# Key_Matrix.net
KiCad netlist of a schematic drawn in EAGLE
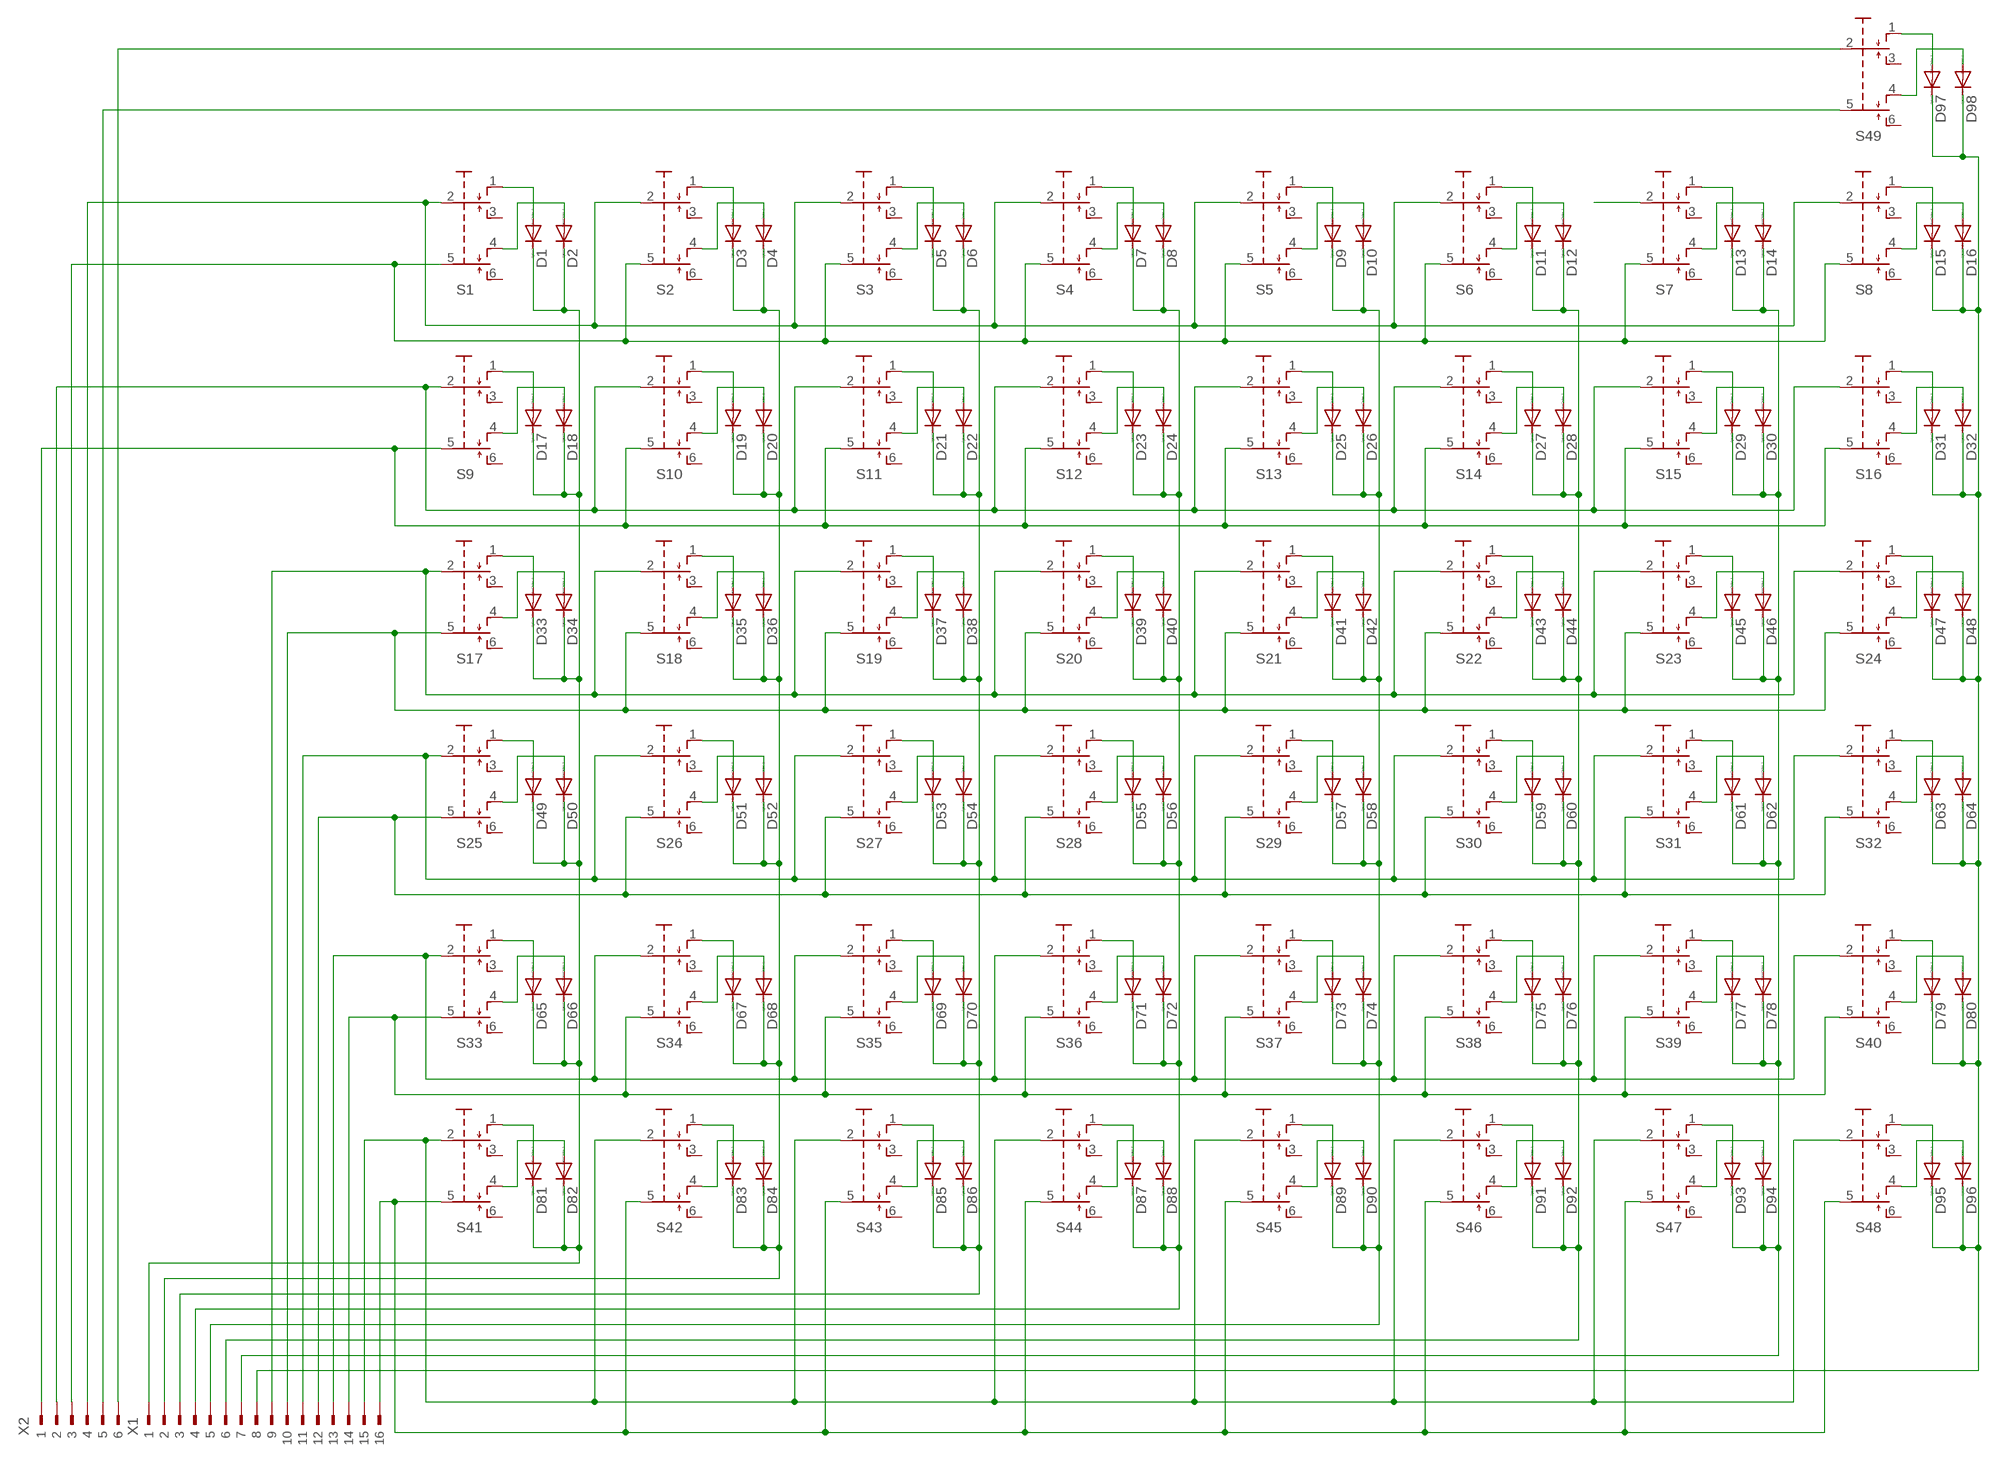
[diagram p0: schematic, sheet 1]

(export (version "E")
  (design (tool "Eeschema 10.0.6"))
  (components
    (comp (ref "D1")
      (value "1N4004")
      (footprint "eagle-import:DO41-10")
      (libsource (lib "eagle-import") (part "1N4004"))
    )
    (comp (ref "D2")
      (value "1N4004")
      (footprint "eagle-import:DO41-10")
      (libsource (lib "eagle-import") (part "1N4004"))
    )
    (comp (ref "D3")
      (value "1N4004")
      (footprint "eagle-import:DO41-10")
      (libsource (lib "eagle-import") (part "1N4004"))
    )
    (comp (ref "D4")
      (value "1N4004")
      (footprint "eagle-import:DO41-10")
      (libsource (lib "eagle-import") (part "1N4004"))
    )
    (comp (ref "D5")
      (value "1N4004")
      (footprint "eagle-import:DO41-10")
      (libsource (lib "eagle-import") (part "1N4004"))
    )
    (comp (ref "D6")
      (value "1N4004")
      (footprint "eagle-import:DO41-10")
      (libsource (lib "eagle-import") (part "1N4004"))
    )
    (comp (ref "D7")
      (value "1N4004")
      (footprint "eagle-import:DO41-10")
      (libsource (lib "eagle-import") (part "1N4004"))
    )
    (comp (ref "D8")
      (value "1N4004")
      (footprint "eagle-import:DO41-10")
      (libsource (lib "eagle-import") (part "1N4004"))
    )
    (comp (ref "D9")
      (value "1N4004")
      (footprint "eagle-import:DO41-10")
      (libsource (lib "eagle-import") (part "1N4004"))
    )
    (comp (ref "D10")
      (value "1N4004")
      (footprint "eagle-import:DO41-10")
      (libsource (lib "eagle-import") (part "1N4004"))
    )
    (comp (ref "D11")
      (value "1N4004")
      (footprint "eagle-import:DO41-10")
      (libsource (lib "eagle-import") (part "1N4004"))
    )
    (comp (ref "D12")
      (value "1N4004")
      (footprint "eagle-import:DO41-10")
      (libsource (lib "eagle-import") (part "1N4004"))
    )
    (comp (ref "D13")
      (value "1N4004")
      (footprint "eagle-import:DO41-10")
      (libsource (lib "eagle-import") (part "1N4004"))
    )
    (comp (ref "D14")
      (value "1N4004")
      (footprint "eagle-import:DO41-10")
      (libsource (lib "eagle-import") (part "1N4004"))
    )
    (comp (ref "D15")
      (value "1N4004")
      (footprint "eagle-import:DO41-10")
      (libsource (lib "eagle-import") (part "1N4004"))
    )
    (comp (ref "D16")
      (value "1N4004")
      (footprint "eagle-import:DO41-10")
      (libsource (lib "eagle-import") (part "1N4004"))
    )
    (comp (ref "D17")
      (value "1N4004")
      (footprint "eagle-import:DO41-10")
      (libsource (lib "eagle-import") (part "1N4004"))
    )
    (comp (ref "D18")
      (value "1N4004")
      (footprint "eagle-import:DO41-10")
      (libsource (lib "eagle-import") (part "1N4004"))
    )
    (comp (ref "D19")
      (value "1N4004")
      (footprint "eagle-import:DO41-10")
      (libsource (lib "eagle-import") (part "1N4004"))
    )
    (comp (ref "D20")
      (value "1N4004")
      (footprint "eagle-import:DO41-10")
      (libsource (lib "eagle-import") (part "1N4004"))
    )
    (comp (ref "D21")
      (value "1N4004")
      (footprint "eagle-import:DO41-10")
      (libsource (lib "eagle-import") (part "1N4004"))
    )
    (comp (ref "D22")
      (value "1N4004")
      (footprint "eagle-import:DO41-10")
      (libsource (lib "eagle-import") (part "1N4004"))
    )
    (comp (ref "D23")
      (value "1N4004")
      (footprint "eagle-import:DO41-10")
      (libsource (lib "eagle-import") (part "1N4004"))
    )
    (comp (ref "D24")
      (value "1N4004")
      (footprint "eagle-import:DO41-10")
      (libsource (lib "eagle-import") (part "1N4004"))
    )
    (comp (ref "D25")
      (value "1N4004")
      (footprint "eagle-import:DO41-10")
      (libsource (lib "eagle-import") (part "1N4004"))
    )
    (comp (ref "D26")
      (value "1N4004")
      (footprint "eagle-import:DO41-10")
      (libsource (lib "eagle-import") (part "1N4004"))
    )
    (comp (ref "D27")
      (value "1N4004")
      (footprint "eagle-import:DO41-10")
      (libsource (lib "eagle-import") (part "1N4004"))
    )
    (comp (ref "D28")
      (value "1N4004")
      (footprint "eagle-import:DO41-10")
      (libsource (lib "eagle-import") (part "1N4004"))
    )
    (comp (ref "D29")
      (value "1N4004")
      (footprint "eagle-import:DO41-10")
      (libsource (lib "eagle-import") (part "1N4004"))
    )
    (comp (ref "D30")
      (value "1N4004")
      (footprint "eagle-import:DO41-10")
      (libsource (lib "eagle-import") (part "1N4004"))
    )
    (comp (ref "D31")
      (value "1N4004")
      (footprint "eagle-import:DO41-10")
      (libsource (lib "eagle-import") (part "1N4004"))
    )
    (comp (ref "D32")
      (value "1N4004")
      (footprint "eagle-import:DO41-10")
      (libsource (lib "eagle-import") (part "1N4004"))
    )
    (comp (ref "D33")
      (value "1N4004")
      (footprint "eagle-import:DO41-10")
      (libsource (lib "eagle-import") (part "1N4004"))
    )
    (comp (ref "D34")
      (value "1N4004")
      (footprint "eagle-import:DO41-10")
      (libsource (lib "eagle-import") (part "1N4004"))
    )
    (comp (ref "D35")
      (value "1N4004")
      (footprint "eagle-import:DO41-10")
      (libsource (lib "eagle-import") (part "1N4004"))
    )
    (comp (ref "D36")
      (value "1N4004")
      (footprint "eagle-import:DO41-10")
      (libsource (lib "eagle-import") (part "1N4004"))
    )
    (comp (ref "D37")
      (value "1N4004")
      (footprint "eagle-import:DO41-10")
      (libsource (lib "eagle-import") (part "1N4004"))
    )
    (comp (ref "D38")
      (value "1N4004")
      (footprint "eagle-import:DO41-10")
      (libsource (lib "eagle-import") (part "1N4004"))
    )
    (comp (ref "D39")
      (value "1N4004")
      (footprint "eagle-import:DO41-10")
      (libsource (lib "eagle-import") (part "1N4004"))
    )
    (comp (ref "D40")
      (value "1N4004")
      (footprint "eagle-import:DO41-10")
      (libsource (lib "eagle-import") (part "1N4004"))
    )
    (comp (ref "D41")
      (value "1N4004")
      (footprint "eagle-import:DO41-10")
      (libsource (lib "eagle-import") (part "1N4004"))
    )
    (comp (ref "D42")
      (value "1N4004")
      (footprint "eagle-import:DO41-10")
      (libsource (lib "eagle-import") (part "1N4004"))
    )
    (comp (ref "D43")
      (value "1N4004")
      (footprint "eagle-import:DO41-10")
      (libsource (lib "eagle-import") (part "1N4004"))
    )
    (comp (ref "D44")
      (value "1N4004")
      (footprint "eagle-import:DO41-10")
      (libsource (lib "eagle-import") (part "1N4004"))
    )
    (comp (ref "D45")
      (value "1N4004")
      (footprint "eagle-import:DO41-10")
      (libsource (lib "eagle-import") (part "1N4004"))
    )
    (comp (ref "D46")
      (value "1N4004")
      (footprint "eagle-import:DO41-10")
      (libsource (lib "eagle-import") (part "1N4004"))
    )
    (comp (ref "D47")
      (value "1N4004")
      (footprint "eagle-import:DO41-10")
      (libsource (lib "eagle-import") (part "1N4004"))
    )
    (comp (ref "D48")
      (value "1N4004")
      (footprint "eagle-import:DO41-10")
      (libsource (lib "eagle-import") (part "1N4004"))
    )
    (comp (ref "D49")
      (value "1N4004")
      (footprint "eagle-import:DO41-10")
      (libsource (lib "eagle-import") (part "1N4004"))
    )
    (comp (ref "D50")
      (value "1N4004")
      (footprint "eagle-import:DO41-10")
      (libsource (lib "eagle-import") (part "1N4004"))
    )
    (comp (ref "D51")
      (value "1N4004")
      (footprint "eagle-import:DO41-10")
      (libsource (lib "eagle-import") (part "1N4004"))
    )
    (comp (ref "D52")
      (value "1N4004")
      (footprint "eagle-import:DO41-10")
      (libsource (lib "eagle-import") (part "1N4004"))
    )
    (comp (ref "D53")
      (value "1N4004")
      (footprint "eagle-import:DO41-10")
      (libsource (lib "eagle-import") (part "1N4004"))
    )
    (comp (ref "D54")
      (value "1N4004")
      (footprint "eagle-import:DO41-10")
      (libsource (lib "eagle-import") (part "1N4004"))
    )
    (comp (ref "D55")
      (value "1N4004")
      (footprint "eagle-import:DO41-10")
      (libsource (lib "eagle-import") (part "1N4004"))
    )
    (comp (ref "D56")
      (value "1N4004")
      (footprint "eagle-import:DO41-10")
      (libsource (lib "eagle-import") (part "1N4004"))
    )
    (comp (ref "D57")
      (value "1N4004")
      (footprint "eagle-import:DO41-10")
      (libsource (lib "eagle-import") (part "1N4004"))
    )
    (comp (ref "D58")
      (value "1N4004")
      (footprint "eagle-import:DO41-10")
      (libsource (lib "eagle-import") (part "1N4004"))
    )
    (comp (ref "D59")
      (value "1N4004")
      (footprint "eagle-import:DO41-10")
      (libsource (lib "eagle-import") (part "1N4004"))
    )
    (comp (ref "D60")
      (value "1N4004")
      (footprint "eagle-import:DO41-10")
      (libsource (lib "eagle-import") (part "1N4004"))
    )
    (comp (ref "D61")
      (value "1N4004")
      (footprint "eagle-import:DO41-10")
      (libsource (lib "eagle-import") (part "1N4004"))
    )
    (comp (ref "D62")
      (value "1N4004")
      (footprint "eagle-import:DO41-10")
      (libsource (lib "eagle-import") (part "1N4004"))
    )
    (comp (ref "D63")
      (value "1N4004")
      (footprint "eagle-import:DO41-10")
      (libsource (lib "eagle-import") (part "1N4004"))
    )
    (comp (ref "D64")
      (value "1N4004")
      (footprint "eagle-import:DO41-10")
      (libsource (lib "eagle-import") (part "1N4004"))
    )
    (comp (ref "D65")
      (value "1N4004")
      (footprint "eagle-import:DO41-10")
      (libsource (lib "eagle-import") (part "1N4004"))
    )
    (comp (ref "D66")
      (value "1N4004")
      (footprint "eagle-import:DO41-10")
      (libsource (lib "eagle-import") (part "1N4004"))
    )
    (comp (ref "D67")
      (value "1N4004")
      (footprint "eagle-import:DO41-10")
      (libsource (lib "eagle-import") (part "1N4004"))
    )
    (comp (ref "D68")
      (value "1N4004")
      (footprint "eagle-import:DO41-10")
      (libsource (lib "eagle-import") (part "1N4004"))
    )
    (comp (ref "D69")
      (value "1N4004")
      (footprint "eagle-import:DO41-10")
      (libsource (lib "eagle-import") (part "1N4004"))
    )
    (comp (ref "D70")
      (value "1N4004")
      (footprint "eagle-import:DO41-10")
      (libsource (lib "eagle-import") (part "1N4004"))
    )
    (comp (ref "D71")
      (value "1N4004")
      (footprint "eagle-import:DO41-10")
      (libsource (lib "eagle-import") (part "1N4004"))
    )
    (comp (ref "D72")
      (value "1N4004")
      (footprint "eagle-import:DO41-10")
      (libsource (lib "eagle-import") (part "1N4004"))
    )
    (comp (ref "D73")
      (value "1N4004")
      (footprint "eagle-import:DO41-10")
      (libsource (lib "eagle-import") (part "1N4004"))
    )
    (comp (ref "D74")
      (value "1N4004")
      (footprint "eagle-import:DO41-10")
      (libsource (lib "eagle-import") (part "1N4004"))
    )
    (comp (ref "D75")
      (value "1N4004")
      (footprint "eagle-import:DO41-10")
      (libsource (lib "eagle-import") (part "1N4004"))
    )
    (comp (ref "D76")
      (value "1N4004")
      (footprint "eagle-import:DO41-10")
      (libsource (lib "eagle-import") (part "1N4004"))
    )
    (comp (ref "D77")
      (value "1N4004")
      (footprint "eagle-import:DO41-10")
      (libsource (lib "eagle-import") (part "1N4004"))
    )
    (comp (ref "D78")
      (value "1N4004")
      (footprint "eagle-import:DO41-10")
      (libsource (lib "eagle-import") (part "1N4004"))
    )
    (comp (ref "D79")
      (value "1N4004")
      (footprint "eagle-import:DO41-10")
      (libsource (lib "eagle-import") (part "1N4004"))
    )
    (comp (ref "D80")
      (value "1N4004")
      (footprint "eagle-import:DO41-10")
      (libsource (lib "eagle-import") (part "1N4004"))
    )
    (comp (ref "D81")
      (value "1N4004")
      (footprint "eagle-import:DO41-10")
      (libsource (lib "eagle-import") (part "1N4004"))
    )
    (comp (ref "D82")
      (value "1N4004")
      (footprint "eagle-import:DO41-10")
      (libsource (lib "eagle-import") (part "1N4004"))
    )
    (comp (ref "D83")
      (value "1N4004")
      (footprint "eagle-import:DO41-10")
      (libsource (lib "eagle-import") (part "1N4004"))
    )
    (comp (ref "D84")
      (value "1N4004")
      (footprint "eagle-import:DO41-10")
      (libsource (lib "eagle-import") (part "1N4004"))
    )
    (comp (ref "D85")
      (value "1N4004")
      (footprint "eagle-import:DO41-10")
      (libsource (lib "eagle-import") (part "1N4004"))
    )
    (comp (ref "D86")
      (value "1N4004")
      (footprint "eagle-import:DO41-10")
      (libsource (lib "eagle-import") (part "1N4004"))
    )
    (comp (ref "D87")
      (value "1N4004")
      (footprint "eagle-import:DO41-10")
      (libsource (lib "eagle-import") (part "1N4004"))
    )
    (comp (ref "D88")
      (value "1N4004")
      (footprint "eagle-import:DO41-10")
      (libsource (lib "eagle-import") (part "1N4004"))
    )
    (comp (ref "D89")
      (value "1N4004")
      (footprint "eagle-import:DO41-10")
      (libsource (lib "eagle-import") (part "1N4004"))
    )
    (comp (ref "D90")
      (value "1N4004")
      (footprint "eagle-import:DO41-10")
      (libsource (lib "eagle-import") (part "1N4004"))
    )
    (comp (ref "D91")
      (value "1N4004")
      (footprint "eagle-import:DO41-10")
      (libsource (lib "eagle-import") (part "1N4004"))
    )
    (comp (ref "D92")
      (value "1N4004")
      (footprint "eagle-import:DO41-10")
      (libsource (lib "eagle-import") (part "1N4004"))
    )
    (comp (ref "D93")
      (value "1N4004")
      (footprint "eagle-import:DO41-10")
      (libsource (lib "eagle-import") (part "1N4004"))
    )
    (comp (ref "D94")
      (value "1N4004")
      (footprint "eagle-import:DO41-10")
      (libsource (lib "eagle-import") (part "1N4004"))
    )
    (comp (ref "D95")
      (value "1N4004")
      (footprint "eagle-import:DO41-10")
      (libsource (lib "eagle-import") (part "1N4004"))
    )
    (comp (ref "D96")
      (value "1N4004")
      (footprint "eagle-import:DO41-10")
      (libsource (lib "eagle-import") (part "1N4004"))
    )
    (comp (ref "D97")
      (value "1N4004")
      (footprint "eagle-import:DO41-10")
      (libsource (lib "eagle-import") (part "1N4004"))
    )
    (comp (ref "D98")
      (value "1N4004")
      (footprint "eagle-import:DO41-10")
      (libsource (lib "eagle-import") (part "1N4004"))
    )
    (comp (ref "S1")
      (value "TL47YO")
      (footprint "eagle-import:TL4XYO")
      (libsource (lib "eagle-import") (part "TL47YO"))
    )
    (comp (ref "S2")
      (value "TL47YO")
      (footprint "eagle-import:TL4XYO")
      (libsource (lib "eagle-import") (part "TL47YO"))
    )
    (comp (ref "S3")
      (value "TL47YO")
      (footprint "eagle-import:TL4XYO")
      (libsource (lib "eagle-import") (part "TL47YO"))
    )
    (comp (ref "S4")
      (value "TL47YO")
      (footprint "eagle-import:TL4XYO")
      (libsource (lib "eagle-import") (part "TL47YO"))
    )
    (comp (ref "S5")
      (value "TL47YO")
      (footprint "eagle-import:TL4XYO")
      (libsource (lib "eagle-import") (part "TL47YO"))
    )
    (comp (ref "S6")
      (value "TL47YO")
      (footprint "eagle-import:TL4XYO")
      (libsource (lib "eagle-import") (part "TL47YO"))
    )
    (comp (ref "S7")
      (value "TL47YO")
      (footprint "eagle-import:TL4XYO")
      (libsource (lib "eagle-import") (part "TL47YO"))
    )
    (comp (ref "S8")
      (value "TL47YO")
      (footprint "eagle-import:TL4XYO")
      (libsource (lib "eagle-import") (part "TL47YO"))
    )
    (comp (ref "S9")
      (value "TL47YO")
      (footprint "eagle-import:TL4XYO")
      (libsource (lib "eagle-import") (part "TL47YO"))
    )
    (comp (ref "S10")
      (value "TL47YO")
      (footprint "eagle-import:TL4XYO")
      (libsource (lib "eagle-import") (part "TL47YO"))
    )
    (comp (ref "S11")
      (value "TL47YO")
      (footprint "eagle-import:TL4XYO")
      (libsource (lib "eagle-import") (part "TL47YO"))
    )
    (comp (ref "S12")
      (value "TL47YO")
      (footprint "eagle-import:TL4XYO")
      (libsource (lib "eagle-import") (part "TL47YO"))
    )
    (comp (ref "S13")
      (value "TL47YO")
      (footprint "eagle-import:TL4XYO")
      (libsource (lib "eagle-import") (part "TL47YO"))
    )
    (comp (ref "S14")
      (value "TL47YO")
      (footprint "eagle-import:TL4XYO")
      (libsource (lib "eagle-import") (part "TL47YO"))
    )
    (comp (ref "S15")
      (value "TL47YO")
      (footprint "eagle-import:TL4XYO")
      (libsource (lib "eagle-import") (part "TL47YO"))
    )
    (comp (ref "S16")
      (value "TL47YO")
      (footprint "eagle-import:TL4XYO")
      (libsource (lib "eagle-import") (part "TL47YO"))
    )
    (comp (ref "S17")
      (value "TL47YO")
      (footprint "eagle-import:TL4XYO")
      (libsource (lib "eagle-import") (part "TL47YO"))
    )
    (comp (ref "S18")
      (value "TL47YO")
      (footprint "eagle-import:TL4XYO")
      (libsource (lib "eagle-import") (part "TL47YO"))
    )
    (comp (ref "S19")
      (value "TL47YO")
      (footprint "eagle-import:TL4XYO")
      (libsource (lib "eagle-import") (part "TL47YO"))
    )
    (comp (ref "S20")
      (value "TL47YO")
      (footprint "eagle-import:TL4XYO")
      (libsource (lib "eagle-import") (part "TL47YO"))
    )
    (comp (ref "S21")
      (value "TL47YO")
      (footprint "eagle-import:TL4XYO")
      (libsource (lib "eagle-import") (part "TL47YO"))
    )
    (comp (ref "S22")
      (value "TL47YO")
      (footprint "eagle-import:TL4XYO")
      (libsource (lib "eagle-import") (part "TL47YO"))
    )
    (comp (ref "S23")
      (value "TL47YO")
      (footprint "eagle-import:TL4XYO")
      (libsource (lib "eagle-import") (part "TL47YO"))
    )
    (comp (ref "S24")
      (value "TL47YO")
      (footprint "eagle-import:TL4XYO")
      (libsource (lib "eagle-import") (part "TL47YO"))
    )
    (comp (ref "S25")
      (value "TL47YO")
      (footprint "eagle-import:TL4XYO")
      (libsource (lib "eagle-import") (part "TL47YO"))
    )
    (comp (ref "S26")
      (value "TL47YO")
      (footprint "eagle-import:TL4XYO")
      (libsource (lib "eagle-import") (part "TL47YO"))
    )
    (comp (ref "S27")
      (value "TL47YO")
      (footprint "eagle-import:TL4XYO")
      (libsource (lib "eagle-import") (part "TL47YO"))
    )
    (comp (ref "S28")
      (value "TL47YO")
      (footprint "eagle-import:TL4XYO")
      (libsource (lib "eagle-import") (part "TL47YO"))
    )
    (comp (ref "S29")
      (value "TL47YO")
      (footprint "eagle-import:TL4XYO")
      (libsource (lib "eagle-import") (part "TL47YO"))
    )
    (comp (ref "S30")
      (value "TL47YO")
      (footprint "eagle-import:TL4XYO")
      (libsource (lib "eagle-import") (part "TL47YO"))
    )
    (comp (ref "S31")
      (value "TL47YO")
      (footprint "eagle-import:TL4XYO")
      (libsource (lib "eagle-import") (part "TL47YO"))
    )
    (comp (ref "S32")
      (value "TL47YO")
      (footprint "eagle-import:TL4XYO")
      (libsource (lib "eagle-import") (part "TL47YO"))
    )
    (comp (ref "S33")
      (value "TL47YO")
      (footprint "eagle-import:TL4XYO")
      (libsource (lib "eagle-import") (part "TL47YO"))
    )
    (comp (ref "S34")
      (value "TL47YO")
      (footprint "eagle-import:TL4XYO")
      (libsource (lib "eagle-import") (part "TL47YO"))
    )
    (comp (ref "S35")
      (value "TL47YO")
      (footprint "eagle-import:TL4XYO")
      (libsource (lib "eagle-import") (part "TL47YO"))
    )
    (comp (ref "S36")
      (value "TL47YO")
      (footprint "eagle-import:TL4XYO")
      (libsource (lib "eagle-import") (part "TL47YO"))
    )
    (comp (ref "S37")
      (value "TL47YO")
      (footprint "eagle-import:TL4XYO")
      (libsource (lib "eagle-import") (part "TL47YO"))
    )
    (comp (ref "S38")
      (value "TL47YO")
      (footprint "eagle-import:TL4XYO")
      (libsource (lib "eagle-import") (part "TL47YO"))
    )
    (comp (ref "S39")
      (value "TL47YO")
      (footprint "eagle-import:TL4XYO")
      (libsource (lib "eagle-import") (part "TL47YO"))
    )
    (comp (ref "S40")
      (value "TL47YO")
      (footprint "eagle-import:TL4XYO")
      (libsource (lib "eagle-import") (part "TL47YO"))
    )
    (comp (ref "S41")
      (value "TL47YO")
      (footprint "eagle-import:TL4XYO")
      (libsource (lib "eagle-import") (part "TL47YO"))
    )
    (comp (ref "S42")
      (value "TL47YO")
      (footprint "eagle-import:TL4XYO")
      (libsource (lib "eagle-import") (part "TL47YO"))
    )
    (comp (ref "S43")
      (value "TL47YO")
      (footprint "eagle-import:TL4XYO")
      (libsource (lib "eagle-import") (part "TL47YO"))
    )
    (comp (ref "S44")
      (value "TL47YO")
      (footprint "eagle-import:TL4XYO")
      (libsource (lib "eagle-import") (part "TL47YO"))
    )
    (comp (ref "S45")
      (value "TL47YO")
      (footprint "eagle-import:TL4XYO")
      (libsource (lib "eagle-import") (part "TL47YO"))
    )
    (comp (ref "S46")
      (value "TL47YO")
      (footprint "eagle-import:TL4XYO")
      (libsource (lib "eagle-import") (part "TL47YO"))
    )
    (comp (ref "S47")
      (value "TL47YO")
      (footprint "eagle-import:TL4XYO")
      (libsource (lib "eagle-import") (part "TL47YO"))
    )
    (comp (ref "S48")
      (value "TL47YO")
      (footprint "eagle-import:TL4XYO")
      (libsource (lib "eagle-import") (part "TL47YO"))
    )
    (comp (ref "S49")
      (value "TL47YO")
      (footprint "eagle-import:TL4XYO")
      (libsource (lib "eagle-import") (part "TL47YO"))
    )
    (comp (ref "X1")
      (value "180G-16")
      (footprint "eagle-import:180G-16")
      (libsource (lib "eagle-import") (part "180G-16"))
    )
    (comp (ref "X2")
      (value "180G-6")
      (footprint "eagle-import:180G-6")
      (libsource (lib "eagle-import") (part "180G-6"))
    )
  )
  (nets
    (net (code "1") (name "Net-(D1-PadC)") (class "Default")
      (node (ref "D1") (pin "C") (pinfunction "C_C") (pintype "passive"))
      (node (ref "D17") (pin "C") (pinfunction "C_C") (pintype "passive"))
      (node (ref "D18") (pin "C") (pinfunction "C_C") (pintype "passive"))
      (node (ref "D2") (pin "C") (pinfunction "C_C") (pintype "passive"))
      (node (ref "D33") (pin "C") (pinfunction "C_C") (pintype "passive"))
      (node (ref "D34") (pin "C") (pinfunction "C_C") (pintype "passive"))
      (node (ref "D49") (pin "C") (pinfunction "C_C") (pintype "passive"))
      (node (ref "D50") (pin "C") (pinfunction "C_C") (pintype "passive"))
      (node (ref "D65") (pin "C") (pinfunction "C_C") (pintype "passive"))
      (node (ref "D66") (pin "C") (pinfunction "C_C") (pintype "passive"))
      (node (ref "D81") (pin "C") (pinfunction "C_C") (pintype "passive"))
      (node (ref "D82") (pin "C") (pinfunction "C_C") (pintype "passive"))
      (node (ref "X1") (pin "1") (pinfunction "1_1") (pintype "passive"))
    )
    (net (code "2") (name "Net-(D10-PadC)") (class "Default")
      (node (ref "D10") (pin "C") (pinfunction "C_C") (pintype "passive"))
      (node (ref "D25") (pin "C") (pinfunction "C_C") (pintype "passive"))
      (node (ref "D26") (pin "C") (pinfunction "C_C") (pintype "passive"))
      (node (ref "D41") (pin "C") (pinfunction "C_C") (pintype "passive"))
      (node (ref "D42") (pin "C") (pinfunction "C_C") (pintype "passive"))
      (node (ref "D57") (pin "C") (pinfunction "C_C") (pintype "passive"))
      (node (ref "D58") (pin "C") (pinfunction "C_C") (pintype "passive"))
      (node (ref "D73") (pin "C") (pinfunction "C_C") (pintype "passive"))
      (node (ref "D74") (pin "C") (pinfunction "C_C") (pintype "passive"))
      (node (ref "D89") (pin "C") (pinfunction "C_C") (pintype "passive"))
      (node (ref "D9") (pin "C") (pinfunction "C_C") (pintype "passive"))
      (node (ref "D90") (pin "C") (pinfunction "C_C") (pintype "passive"))
      (node (ref "X1") (pin "5") (pinfunction "5_5") (pintype "passive"))
    )
    (net (code "3") (name "Net-(D11-PadC)") (class "Default")
      (node (ref "D11") (pin "C") (pinfunction "C_C") (pintype "passive"))
      (node (ref "D12") (pin "C") (pinfunction "C_C") (pintype "passive"))
      (node (ref "D27") (pin "C") (pinfunction "C_C") (pintype "passive"))
      (node (ref "D28") (pin "C") (pinfunction "C_C") (pintype "passive"))
      (node (ref "D43") (pin "C") (pinfunction "C_C") (pintype "passive"))
      (node (ref "D44") (pin "C") (pinfunction "C_C") (pintype "passive"))
      (node (ref "D59") (pin "C") (pinfunction "C_C") (pintype "passive"))
      (node (ref "D60") (pin "C") (pinfunction "C_C") (pintype "passive"))
      (node (ref "D75") (pin "C") (pinfunction "C_C") (pintype "passive"))
      (node (ref "D76") (pin "C") (pinfunction "C_C") (pintype "passive"))
      (node (ref "D91") (pin "C") (pinfunction "C_C") (pintype "passive"))
      (node (ref "D92") (pin "C") (pinfunction "C_C") (pintype "passive"))
      (node (ref "X1") (pin "6") (pinfunction "6_6") (pintype "passive"))
    )
    (net (code "4") (name "Net-(D13-PadC)") (class "Default")
      (node (ref "D13") (pin "C") (pinfunction "C_C") (pintype "passive"))
      (node (ref "D14") (pin "C") (pinfunction "C_C") (pintype "passive"))
      (node (ref "D29") (pin "C") (pinfunction "C_C") (pintype "passive"))
      (node (ref "D30") (pin "C") (pinfunction "C_C") (pintype "passive"))
      (node (ref "D45") (pin "C") (pinfunction "C_C") (pintype "passive"))
      (node (ref "D46") (pin "C") (pinfunction "C_C") (pintype "passive"))
      (node (ref "D61") (pin "C") (pinfunction "C_C") (pintype "passive"))
      (node (ref "D62") (pin "C") (pinfunction "C_C") (pintype "passive"))
      (node (ref "D77") (pin "C") (pinfunction "C_C") (pintype "passive"))
      (node (ref "D78") (pin "C") (pinfunction "C_C") (pintype "passive"))
      (node (ref "D93") (pin "C") (pinfunction "C_C") (pintype "passive"))
      (node (ref "D94") (pin "C") (pinfunction "C_C") (pintype "passive"))
      (node (ref "X1") (pin "7") (pinfunction "7_7") (pintype "passive"))
    )
    (net (code "5") (name "Net-(D15-PadC)") (class "Default")
      (node (ref "D15") (pin "C") (pinfunction "C_C") (pintype "passive"))
      (node (ref "D16") (pin "C") (pinfunction "C_C") (pintype "passive"))
      (node (ref "D31") (pin "C") (pinfunction "C_C") (pintype "passive"))
      (node (ref "D32") (pin "C") (pinfunction "C_C") (pintype "passive"))
      (node (ref "D47") (pin "C") (pinfunction "C_C") (pintype "passive"))
      (node (ref "D48") (pin "C") (pinfunction "C_C") (pintype "passive"))
      (node (ref "D63") (pin "C") (pinfunction "C_C") (pintype "passive"))
      (node (ref "D64") (pin "C") (pinfunction "C_C") (pintype "passive"))
      (node (ref "D79") (pin "C") (pinfunction "C_C") (pintype "passive"))
      (node (ref "D80") (pin "C") (pinfunction "C_C") (pintype "passive"))
      (node (ref "D95") (pin "C") (pinfunction "C_C") (pintype "passive"))
      (node (ref "D96") (pin "C") (pinfunction "C_C") (pintype "passive"))
      (node (ref "D97") (pin "C") (pinfunction "C_C") (pintype "passive"))
      (node (ref "D98") (pin "C") (pinfunction "C_C") (pintype "passive"))
      (node (ref "X1") (pin "8") (pinfunction "8_8") (pintype "passive"))
    )
    (net (code "6") (name "Net-(D19-PadC)") (class "Default")
      (node (ref "D19") (pin "C") (pinfunction "C_C") (pintype "passive"))
      (node (ref "D20") (pin "C") (pinfunction "C_C") (pintype "passive"))
      (node (ref "D3") (pin "C") (pinfunction "C_C") (pintype "passive"))
      (node (ref "D35") (pin "C") (pinfunction "C_C") (pintype "passive"))
      (node (ref "D36") (pin "C") (pinfunction "C_C") (pintype "passive"))
      (node (ref "D4") (pin "C") (pinfunction "C_C") (pintype "passive"))
      (node (ref "D51") (pin "C") (pinfunction "C_C") (pintype "passive"))
      (node (ref "D52") (pin "C") (pinfunction "C_C") (pintype "passive"))
      (node (ref "D67") (pin "C") (pinfunction "C_C") (pintype "passive"))
      (node (ref "D68") (pin "C") (pinfunction "C_C") (pintype "passive"))
      (node (ref "D83") (pin "C") (pinfunction "C_C") (pintype "passive"))
      (node (ref "D84") (pin "C") (pinfunction "C_C") (pintype "passive"))
      (node (ref "X1") (pin "2") (pinfunction "2_2") (pintype "passive"))
    )
    (net (code "7") (name "Net-(D21-PadC)") (class "Default")
      (node (ref "D21") (pin "C") (pinfunction "C_C") (pintype "passive"))
      (node (ref "D22") (pin "C") (pinfunction "C_C") (pintype "passive"))
      (node (ref "D37") (pin "C") (pinfunction "C_C") (pintype "passive"))
      (node (ref "D38") (pin "C") (pinfunction "C_C") (pintype "passive"))
      (node (ref "D5") (pin "C") (pinfunction "C_C") (pintype "passive"))
      (node (ref "D53") (pin "C") (pinfunction "C_C") (pintype "passive"))
      (node (ref "D54") (pin "C") (pinfunction "C_C") (pintype "passive"))
      (node (ref "D6") (pin "C") (pinfunction "C_C") (pintype "passive"))
      (node (ref "D69") (pin "C") (pinfunction "C_C") (pintype "passive"))
      (node (ref "D70") (pin "C") (pinfunction "C_C") (pintype "passive"))
      (node (ref "D85") (pin "C") (pinfunction "C_C") (pintype "passive"))
      (node (ref "D86") (pin "C") (pinfunction "C_C") (pintype "passive"))
      (node (ref "X1") (pin "3") (pinfunction "3_3") (pintype "passive"))
    )
    (net (code "8") (name "Net-(D23-PadC)") (class "Default")
      (node (ref "D23") (pin "C") (pinfunction "C_C") (pintype "passive"))
      (node (ref "D24") (pin "C") (pinfunction "C_C") (pintype "passive"))
      (node (ref "D39") (pin "C") (pinfunction "C_C") (pintype "passive"))
      (node (ref "D40") (pin "C") (pinfunction "C_C") (pintype "passive"))
      (node (ref "D55") (pin "C") (pinfunction "C_C") (pintype "passive"))
      (node (ref "D56") (pin "C") (pinfunction "C_C") (pintype "passive"))
      (node (ref "D7") (pin "C") (pinfunction "C_C") (pintype "passive"))
      (node (ref "D71") (pin "C") (pinfunction "C_C") (pintype "passive"))
      (node (ref "D72") (pin "C") (pinfunction "C_C") (pintype "passive"))
      (node (ref "D8") (pin "C") (pinfunction "C_C") (pintype "passive"))
      (node (ref "D87") (pin "C") (pinfunction "C_C") (pintype "passive"))
      (node (ref "D88") (pin "C") (pinfunction "C_C") (pintype "passive"))
      (node (ref "X1") (pin "4") (pinfunction "4_4") (pintype "passive"))
    )
    (net (code "9") (name "Net-(S1-O)") (class "Default")
      (node (ref "D1") (pin "A") (pinfunction "A_A") (pintype "passive"))
      (node (ref "S1") (pin "1") (pinfunction "O_1") (pintype "passive"))
    )
    (net (code "10") (name "Net-(S1-O1)") (class "Default")
      (node (ref "D2") (pin "A") (pinfunction "A_A") (pintype "passive"))
      (node (ref "S1") (pin "4") (pinfunction "O1_4") (pintype "passive"))
    )
    (net (code "11") (name "Net-(S1-P)") (class "Default")
      (node (ref "S1") (pin "2") (pinfunction "P_2") (pintype "passive"))
      (node (ref "S2") (pin "2") (pinfunction "P_2") (pintype "passive"))
      (node (ref "S3") (pin "2") (pinfunction "P_2") (pintype "passive"))
      (node (ref "S4") (pin "2") (pinfunction "P_2") (pintype "passive"))
      (node (ref "S5") (pin "2") (pinfunction "P_2") (pintype "passive"))
      (node (ref "S6") (pin "2") (pinfunction "P_2") (pintype "passive"))
      (node (ref "S8") (pin "2") (pinfunction "P_2") (pintype "passive"))
      (node (ref "X2") (pin "4") (pinfunction "4_4") (pintype "passive"))
    )
    (net (code "12") (name "Net-(S1-P1)") (class "Default")
      (node (ref "S1") (pin "5") (pinfunction "P1_5") (pintype "passive"))
      (node (ref "S2") (pin "5") (pinfunction "P1_5") (pintype "passive"))
      (node (ref "S3") (pin "5") (pinfunction "P1_5") (pintype "passive"))
      (node (ref "S4") (pin "5") (pinfunction "P1_5") (pintype "passive"))
      (node (ref "S5") (pin "5") (pinfunction "P1_5") (pintype "passive"))
      (node (ref "S6") (pin "5") (pinfunction "P1_5") (pintype "passive"))
      (node (ref "S7") (pin "5") (pinfunction "P1_5") (pintype "passive"))
      (node (ref "S8") (pin "5") (pinfunction "P1_5") (pintype "passive"))
      (node (ref "X2") (pin "3") (pinfunction "3_3") (pintype "passive"))
    )
    (net (code "13") (name "Net-(S2-O)") (class "Default")
      (node (ref "D3") (pin "A") (pinfunction "A_A") (pintype "passive"))
      (node (ref "S2") (pin "1") (pinfunction "O_1") (pintype "passive"))
    )
    (net (code "14") (name "Net-(S2-O1)") (class "Default")
      (node (ref "D4") (pin "A") (pinfunction "A_A") (pintype "passive"))
      (node (ref "S2") (pin "4") (pinfunction "O1_4") (pintype "passive"))
    )
    (net (code "15") (name "Net-(S3-O)") (class "Default")
      (node (ref "D5") (pin "A") (pinfunction "A_A") (pintype "passive"))
      (node (ref "S3") (pin "1") (pinfunction "O_1") (pintype "passive"))
    )
    (net (code "16") (name "Net-(S3-O1)") (class "Default")
      (node (ref "D6") (pin "A") (pinfunction "A_A") (pintype "passive"))
      (node (ref "S3") (pin "4") (pinfunction "O1_4") (pintype "passive"))
    )
    (net (code "17") (name "Net-(S4-O)") (class "Default")
      (node (ref "D7") (pin "A") (pinfunction "A_A") (pintype "passive"))
      (node (ref "S4") (pin "1") (pinfunction "O_1") (pintype "passive"))
    )
    (net (code "18") (name "Net-(S4-O1)") (class "Default")
      (node (ref "D8") (pin "A") (pinfunction "A_A") (pintype "passive"))
      (node (ref "S4") (pin "4") (pinfunction "O1_4") (pintype "passive"))
    )
    (net (code "19") (name "Net-(S5-O)") (class "Default")
      (node (ref "D9") (pin "A") (pinfunction "A_A") (pintype "passive"))
      (node (ref "S5") (pin "1") (pinfunction "O_1") (pintype "passive"))
    )
    (net (code "20") (name "Net-(S5-O1)") (class "Default")
      (node (ref "D10") (pin "A") (pinfunction "A_A") (pintype "passive"))
      (node (ref "S5") (pin "4") (pinfunction "O1_4") (pintype "passive"))
    )
    (net (code "21") (name "Net-(S6-O)") (class "Default")
      (node (ref "D11") (pin "A") (pinfunction "A_A") (pintype "passive"))
      (node (ref "S6") (pin "1") (pinfunction "O_1") (pintype "passive"))
    )
    (net (code "22") (name "Net-(S6-O1)") (class "Default")
      (node (ref "D12") (pin "A") (pinfunction "A_A") (pintype "passive"))
      (node (ref "S6") (pin "4") (pinfunction "O1_4") (pintype "passive"))
    )
    (net (code "23") (name "Net-(S7-O)") (class "Default")
      (node (ref "D13") (pin "A") (pinfunction "A_A") (pintype "passive"))
      (node (ref "S7") (pin "1") (pinfunction "O_1") (pintype "passive"))
    )
    (net (code "24") (name "Net-(S7-O1)") (class "Default")
      (node (ref "D14") (pin "A") (pinfunction "A_A") (pintype "passive"))
      (node (ref "S7") (pin "4") (pinfunction "O1_4") (pintype "passive"))
    )
    (net (code "25") (name "Net-(S8-O)") (class "Default")
      (node (ref "D15") (pin "A") (pinfunction "A_A") (pintype "passive"))
      (node (ref "S8") (pin "1") (pinfunction "O_1") (pintype "passive"))
    )
    (net (code "26") (name "Net-(S8-O1)") (class "Default")
      (node (ref "D16") (pin "A") (pinfunction "A_A") (pintype "passive"))
      (node (ref "S8") (pin "4") (pinfunction "O1_4") (pintype "passive"))
    )
    (net (code "27") (name "Net-(S9-O)") (class "Default")
      (node (ref "D17") (pin "A") (pinfunction "A_A") (pintype "passive"))
      (node (ref "S9") (pin "1") (pinfunction "O_1") (pintype "passive"))
    )
    (net (code "28") (name "Net-(S9-O1)") (class "Default")
      (node (ref "D18") (pin "A") (pinfunction "A_A") (pintype "passive"))
      (node (ref "S9") (pin "4") (pinfunction "O1_4") (pintype "passive"))
    )
    (net (code "29") (name "Net-(S10-O)") (class "Default")
      (node (ref "D19") (pin "A") (pinfunction "A_A") (pintype "passive"))
      (node (ref "S10") (pin "1") (pinfunction "O_1") (pintype "passive"))
    )
    (net (code "30") (name "Net-(S10-O1)") (class "Default")
      (node (ref "D20") (pin "A") (pinfunction "A_A") (pintype "passive"))
      (node (ref "S10") (pin "4") (pinfunction "O1_4") (pintype "passive"))
    )
    (net (code "31") (name "Net-(S10-P)") (class "Default")
      (node (ref "S10") (pin "2") (pinfunction "P_2") (pintype "passive"))
      (node (ref "S11") (pin "2") (pinfunction "P_2") (pintype "passive"))
      (node (ref "S12") (pin "2") (pinfunction "P_2") (pintype "passive"))
      (node (ref "S13") (pin "2") (pinfunction "P_2") (pintype "passive"))
      (node (ref "S14") (pin "2") (pinfunction "P_2") (pintype "passive"))
      (node (ref "S15") (pin "2") (pinfunction "P_2") (pintype "passive"))
      (node (ref "S16") (pin "2") (pinfunction "P_2") (pintype "passive"))
      (node (ref "S9") (pin "2") (pinfunction "P_2") (pintype "passive"))
      (node (ref "X2") (pin "2") (pinfunction "2_2") (pintype "passive"))
    )
    (net (code "32") (name "Net-(S10-P1)") (class "Default")
      (node (ref "S10") (pin "5") (pinfunction "P1_5") (pintype "passive"))
      (node (ref "S11") (pin "5") (pinfunction "P1_5") (pintype "passive"))
      (node (ref "S12") (pin "5") (pinfunction "P1_5") (pintype "passive"))
      (node (ref "S13") (pin "5") (pinfunction "P1_5") (pintype "passive"))
      (node (ref "S14") (pin "5") (pinfunction "P1_5") (pintype "passive"))
      (node (ref "S15") (pin "5") (pinfunction "P1_5") (pintype "passive"))
      (node (ref "S16") (pin "5") (pinfunction "P1_5") (pintype "passive"))
      (node (ref "S9") (pin "5") (pinfunction "P1_5") (pintype "passive"))
      (node (ref "X2") (pin "1") (pinfunction "1_1") (pintype "passive"))
    )
    (net (code "33") (name "Net-(S11-O)") (class "Default")
      (node (ref "D21") (pin "A") (pinfunction "A_A") (pintype "passive"))
      (node (ref "S11") (pin "1") (pinfunction "O_1") (pintype "passive"))
    )
    (net (code "34") (name "Net-(S11-O1)") (class "Default")
      (node (ref "D22") (pin "A") (pinfunction "A_A") (pintype "passive"))
      (node (ref "S11") (pin "4") (pinfunction "O1_4") (pintype "passive"))
    )
    (net (code "35") (name "Net-(S12-O)") (class "Default")
      (node (ref "D23") (pin "A") (pinfunction "A_A") (pintype "passive"))
      (node (ref "S12") (pin "1") (pinfunction "O_1") (pintype "passive"))
    )
    (net (code "36") (name "Net-(S12-O1)") (class "Default")
      (node (ref "D24") (pin "A") (pinfunction "A_A") (pintype "passive"))
      (node (ref "S12") (pin "4") (pinfunction "O1_4") (pintype "passive"))
    )
    (net (code "37") (name "Net-(S13-O)") (class "Default")
      (node (ref "D25") (pin "A") (pinfunction "A_A") (pintype "passive"))
      (node (ref "S13") (pin "1") (pinfunction "O_1") (pintype "passive"))
    )
    (net (code "38") (name "Net-(S13-O1)") (class "Default")
      (node (ref "D26") (pin "A") (pinfunction "A_A") (pintype "passive"))
      (node (ref "S13") (pin "4") (pinfunction "O1_4") (pintype "passive"))
    )
    (net (code "39") (name "Net-(S14-O)") (class "Default")
      (node (ref "D27") (pin "A") (pinfunction "A_A") (pintype "passive"))
      (node (ref "S14") (pin "1") (pinfunction "O_1") (pintype "passive"))
    )
    (net (code "40") (name "Net-(S14-O1)") (class "Default")
      (node (ref "D28") (pin "A") (pinfunction "A_A") (pintype "passive"))
      (node (ref "S14") (pin "4") (pinfunction "O1_4") (pintype "passive"))
    )
    (net (code "41") (name "Net-(S15-O)") (class "Default")
      (node (ref "D29") (pin "A") (pinfunction "A_A") (pintype "passive"))
      (node (ref "S15") (pin "1") (pinfunction "O_1") (pintype "passive"))
    )
    (net (code "42") (name "Net-(S15-O1)") (class "Default")
      (node (ref "D30") (pin "A") (pinfunction "A_A") (pintype "passive"))
      (node (ref "S15") (pin "4") (pinfunction "O1_4") (pintype "passive"))
    )
    (net (code "43") (name "Net-(S16-O)") (class "Default")
      (node (ref "D31") (pin "A") (pinfunction "A_A") (pintype "passive"))
      (node (ref "S16") (pin "1") (pinfunction "O_1") (pintype "passive"))
    )
    (net (code "44") (name "Net-(S16-O1)") (class "Default")
      (node (ref "D32") (pin "A") (pinfunction "A_A") (pintype "passive"))
      (node (ref "S16") (pin "4") (pinfunction "O1_4") (pintype "passive"))
    )
    (net (code "45") (name "Net-(S17-O)") (class "Default")
      (node (ref "D33") (pin "A") (pinfunction "A_A") (pintype "passive"))
      (node (ref "S17") (pin "1") (pinfunction "O_1") (pintype "passive"))
    )
    (net (code "46") (name "Net-(S17-O1)") (class "Default")
      (node (ref "D34") (pin "A") (pinfunction "A_A") (pintype "passive"))
      (node (ref "S17") (pin "4") (pinfunction "O1_4") (pintype "passive"))
    )
    (net (code "47") (name "Net-(S17-P)") (class "Default")
      (node (ref "S17") (pin "2") (pinfunction "P_2") (pintype "passive"))
      (node (ref "S18") (pin "2") (pinfunction "P_2") (pintype "passive"))
      (node (ref "S19") (pin "2") (pinfunction "P_2") (pintype "passive"))
      (node (ref "S20") (pin "2") (pinfunction "P_2") (pintype "passive"))
      (node (ref "S21") (pin "2") (pinfunction "P_2") (pintype "passive"))
      (node (ref "S22") (pin "2") (pinfunction "P_2") (pintype "passive"))
      (node (ref "S23") (pin "2") (pinfunction "P_2") (pintype "passive"))
      (node (ref "S24") (pin "2") (pinfunction "P_2") (pintype "passive"))
      (node (ref "X1") (pin "9") (pinfunction "9_9") (pintype "passive"))
    )
    (net (code "48") (name "Net-(S17-P1)") (class "Default")
      (node (ref "S17") (pin "5") (pinfunction "P1_5") (pintype "passive"))
      (node (ref "S18") (pin "5") (pinfunction "P1_5") (pintype "passive"))
      (node (ref "S19") (pin "5") (pinfunction "P1_5") (pintype "passive"))
      (node (ref "S20") (pin "5") (pinfunction "P1_5") (pintype "passive"))
      (node (ref "S21") (pin "5") (pinfunction "P1_5") (pintype "passive"))
      (node (ref "S22") (pin "5") (pinfunction "P1_5") (pintype "passive"))
      (node (ref "S23") (pin "5") (pinfunction "P1_5") (pintype "passive"))
      (node (ref "S24") (pin "5") (pinfunction "P1_5") (pintype "passive"))
      (node (ref "X1") (pin "10") (pinfunction "10_10") (pintype "passive"))
    )
    (net (code "49") (name "Net-(S18-O)") (class "Default")
      (node (ref "D35") (pin "A") (pinfunction "A_A") (pintype "passive"))
      (node (ref "S18") (pin "1") (pinfunction "O_1") (pintype "passive"))
    )
    (net (code "50") (name "Net-(S18-O1)") (class "Default")
      (node (ref "D36") (pin "A") (pinfunction "A_A") (pintype "passive"))
      (node (ref "S18") (pin "4") (pinfunction "O1_4") (pintype "passive"))
    )
    (net (code "51") (name "Net-(S19-O)") (class "Default")
      (node (ref "D37") (pin "A") (pinfunction "A_A") (pintype "passive"))
      (node (ref "S19") (pin "1") (pinfunction "O_1") (pintype "passive"))
    )
    (net (code "52") (name "Net-(S19-O1)") (class "Default")
      (node (ref "D38") (pin "A") (pinfunction "A_A") (pintype "passive"))
      (node (ref "S19") (pin "4") (pinfunction "O1_4") (pintype "passive"))
    )
    (net (code "53") (name "Net-(S20-O)") (class "Default")
      (node (ref "D39") (pin "A") (pinfunction "A_A") (pintype "passive"))
      (node (ref "S20") (pin "1") (pinfunction "O_1") (pintype "passive"))
    )
    (net (code "54") (name "Net-(S20-O1)") (class "Default")
      (node (ref "D40") (pin "A") (pinfunction "A_A") (pintype "passive"))
      (node (ref "S20") (pin "4") (pinfunction "O1_4") (pintype "passive"))
    )
    (net (code "55") (name "Net-(S21-O)") (class "Default")
      (node (ref "D41") (pin "A") (pinfunction "A_A") (pintype "passive"))
      (node (ref "S21") (pin "1") (pinfunction "O_1") (pintype "passive"))
    )
    (net (code "56") (name "Net-(S21-O1)") (class "Default")
      (node (ref "D42") (pin "A") (pinfunction "A_A") (pintype "passive"))
      (node (ref "S21") (pin "4") (pinfunction "O1_4") (pintype "passive"))
    )
    (net (code "57") (name "Net-(S22-O)") (class "Default")
      (node (ref "D43") (pin "A") (pinfunction "A_A") (pintype "passive"))
      (node (ref "S22") (pin "1") (pinfunction "O_1") (pintype "passive"))
    )
    (net (code "58") (name "Net-(S22-O1)") (class "Default")
      (node (ref "D44") (pin "A") (pinfunction "A_A") (pintype "passive"))
      (node (ref "S22") (pin "4") (pinfunction "O1_4") (pintype "passive"))
    )
    (net (code "59") (name "Net-(S23-O)") (class "Default")
      (node (ref "D45") (pin "A") (pinfunction "A_A") (pintype "passive"))
      (node (ref "S23") (pin "1") (pinfunction "O_1") (pintype "passive"))
    )
    (net (code "60") (name "Net-(S23-O1)") (class "Default")
      (node (ref "D46") (pin "A") (pinfunction "A_A") (pintype "passive"))
      (node (ref "S23") (pin "4") (pinfunction "O1_4") (pintype "passive"))
    )
    (net (code "61") (name "Net-(S24-O)") (class "Default")
      (node (ref "D47") (pin "A") (pinfunction "A_A") (pintype "passive"))
      (node (ref "S24") (pin "1") (pinfunction "O_1") (pintype "passive"))
    )
    (net (code "62") (name "Net-(S24-O1)") (class "Default")
      (node (ref "D48") (pin "A") (pinfunction "A_A") (pintype "passive"))
      (node (ref "S24") (pin "4") (pinfunction "O1_4") (pintype "passive"))
    )
    (net (code "63") (name "Net-(S25-O)") (class "Default")
      (node (ref "D49") (pin "A") (pinfunction "A_A") (pintype "passive"))
      (node (ref "S25") (pin "1") (pinfunction "O_1") (pintype "passive"))
    )
    (net (code "64") (name "Net-(S25-O1)") (class "Default")
      (node (ref "D50") (pin "A") (pinfunction "A_A") (pintype "passive"))
      (node (ref "S25") (pin "4") (pinfunction "O1_4") (pintype "passive"))
    )
    (net (code "65") (name "Net-(S25-P)") (class "Default")
      (node (ref "S25") (pin "2") (pinfunction "P_2") (pintype "passive"))
      (node (ref "S26") (pin "2") (pinfunction "P_2") (pintype "passive"))
      (node (ref "S27") (pin "2") (pinfunction "P_2") (pintype "passive"))
      (node (ref "S28") (pin "2") (pinfunction "P_2") (pintype "passive"))
      (node (ref "S29") (pin "2") (pinfunction "P_2") (pintype "passive"))
      (node (ref "S30") (pin "2") (pinfunction "P_2") (pintype "passive"))
      (node (ref "S31") (pin "2") (pinfunction "P_2") (pintype "passive"))
      (node (ref "S32") (pin "2") (pinfunction "P_2") (pintype "passive"))
      (node (ref "X1") (pin "11") (pinfunction "11_11") (pintype "passive"))
    )
    (net (code "66") (name "Net-(S25-P1)") (class "Default")
      (node (ref "S25") (pin "5") (pinfunction "P1_5") (pintype "passive"))
      (node (ref "S26") (pin "5") (pinfunction "P1_5") (pintype "passive"))
      (node (ref "S27") (pin "5") (pinfunction "P1_5") (pintype "passive"))
      (node (ref "S28") (pin "5") (pinfunction "P1_5") (pintype "passive"))
      (node (ref "S29") (pin "5") (pinfunction "P1_5") (pintype "passive"))
      (node (ref "S30") (pin "5") (pinfunction "P1_5") (pintype "passive"))
      (node (ref "S31") (pin "5") (pinfunction "P1_5") (pintype "passive"))
      (node (ref "S32") (pin "5") (pinfunction "P1_5") (pintype "passive"))
      (node (ref "X1") (pin "12") (pinfunction "12_12") (pintype "passive"))
    )
    (net (code "67") (name "Net-(S26-O)") (class "Default")
      (node (ref "D51") (pin "A") (pinfunction "A_A") (pintype "passive"))
      (node (ref "S26") (pin "1") (pinfunction "O_1") (pintype "passive"))
    )
    (net (code "68") (name "Net-(S26-O1)") (class "Default")
      (node (ref "D52") (pin "A") (pinfunction "A_A") (pintype "passive"))
      (node (ref "S26") (pin "4") (pinfunction "O1_4") (pintype "passive"))
    )
    (net (code "69") (name "Net-(S27-O)") (class "Default")
      (node (ref "D53") (pin "A") (pinfunction "A_A") (pintype "passive"))
      (node (ref "S27") (pin "1") (pinfunction "O_1") (pintype "passive"))
    )
    (net (code "70") (name "Net-(S27-O1)") (class "Default")
      (node (ref "D54") (pin "A") (pinfunction "A_A") (pintype "passive"))
      (node (ref "S27") (pin "4") (pinfunction "O1_4") (pintype "passive"))
    )
    (net (code "71") (name "Net-(S28-O)") (class "Default")
      (node (ref "D55") (pin "A") (pinfunction "A_A") (pintype "passive"))
      (node (ref "S28") (pin "1") (pinfunction "O_1") (pintype "passive"))
    )
    (net (code "72") (name "Net-(S28-O1)") (class "Default")
      (node (ref "D56") (pin "A") (pinfunction "A_A") (pintype "passive"))
      (node (ref "S28") (pin "4") (pinfunction "O1_4") (pintype "passive"))
    )
    (net (code "73") (name "Net-(S29-O)") (class "Default")
      (node (ref "D57") (pin "A") (pinfunction "A_A") (pintype "passive"))
      (node (ref "S29") (pin "1") (pinfunction "O_1") (pintype "passive"))
    )
    (net (code "74") (name "Net-(S29-O1)") (class "Default")
      (node (ref "D58") (pin "A") (pinfunction "A_A") (pintype "passive"))
      (node (ref "S29") (pin "4") (pinfunction "O1_4") (pintype "passive"))
    )
    (net (code "75") (name "Net-(S30-O)") (class "Default")
      (node (ref "D59") (pin "A") (pinfunction "A_A") (pintype "passive"))
      (node (ref "S30") (pin "1") (pinfunction "O_1") (pintype "passive"))
    )
    (net (code "76") (name "Net-(S30-O1)") (class "Default")
      (node (ref "D60") (pin "A") (pinfunction "A_A") (pintype "passive"))
      (node (ref "S30") (pin "4") (pinfunction "O1_4") (pintype "passive"))
    )
    (net (code "77") (name "Net-(S31-O)") (class "Default")
      (node (ref "D61") (pin "A") (pinfunction "A_A") (pintype "passive"))
      (node (ref "S31") (pin "1") (pinfunction "O_1") (pintype "passive"))
    )
    (net (code "78") (name "Net-(S31-O1)") (class "Default")
      (node (ref "D62") (pin "A") (pinfunction "A_A") (pintype "passive"))
      (node (ref "S31") (pin "4") (pinfunction "O1_4") (pintype "passive"))
    )
    (net (code "79") (name "Net-(S32-O)") (class "Default")
      (node (ref "D63") (pin "A") (pinfunction "A_A") (pintype "passive"))
      (node (ref "S32") (pin "1") (pinfunction "O_1") (pintype "passive"))
    )
    (net (code "80") (name "Net-(S32-O1)") (class "Default")
      (node (ref "D64") (pin "A") (pinfunction "A_A") (pintype "passive"))
      (node (ref "S32") (pin "4") (pinfunction "O1_4") (pintype "passive"))
    )
    (net (code "81") (name "Net-(S33-O)") (class "Default")
      (node (ref "D65") (pin "A") (pinfunction "A_A") (pintype "passive"))
      (node (ref "S33") (pin "1") (pinfunction "O_1") (pintype "passive"))
    )
    (net (code "82") (name "Net-(S33-O1)") (class "Default")
      (node (ref "D66") (pin "A") (pinfunction "A_A") (pintype "passive"))
      (node (ref "S33") (pin "4") (pinfunction "O1_4") (pintype "passive"))
    )
    (net (code "83") (name "Net-(S33-P)") (class "Default")
      (node (ref "S33") (pin "2") (pinfunction "P_2") (pintype "passive"))
      (node (ref "S34") (pin "2") (pinfunction "P_2") (pintype "passive"))
      (node (ref "S35") (pin "2") (pinfunction "P_2") (pintype "passive"))
      (node (ref "S36") (pin "2") (pinfunction "P_2") (pintype "passive"))
      (node (ref "S37") (pin "2") (pinfunction "P_2") (pintype "passive"))
      (node (ref "S38") (pin "2") (pinfunction "P_2") (pintype "passive"))
      (node (ref "S39") (pin "2") (pinfunction "P_2") (pintype "passive"))
      (node (ref "S40") (pin "2") (pinfunction "P_2") (pintype "passive"))
      (node (ref "X1") (pin "13") (pinfunction "13_13") (pintype "passive"))
    )
    (net (code "84") (name "Net-(S33-P1)") (class "Default")
      (node (ref "S33") (pin "5") (pinfunction "P1_5") (pintype "passive"))
      (node (ref "S34") (pin "5") (pinfunction "P1_5") (pintype "passive"))
      (node (ref "S35") (pin "5") (pinfunction "P1_5") (pintype "passive"))
      (node (ref "S36") (pin "5") (pinfunction "P1_5") (pintype "passive"))
      (node (ref "S37") (pin "5") (pinfunction "P1_5") (pintype "passive"))
      (node (ref "S38") (pin "5") (pinfunction "P1_5") (pintype "passive"))
      (node (ref "S39") (pin "5") (pinfunction "P1_5") (pintype "passive"))
      (node (ref "S40") (pin "5") (pinfunction "P1_5") (pintype "passive"))
      (node (ref "X1") (pin "14") (pinfunction "14_14") (pintype "passive"))
    )
    (net (code "85") (name "Net-(S34-O)") (class "Default")
      (node (ref "D67") (pin "A") (pinfunction "A_A") (pintype "passive"))
      (node (ref "S34") (pin "1") (pinfunction "O_1") (pintype "passive"))
    )
    (net (code "86") (name "Net-(S34-O1)") (class "Default")
      (node (ref "D68") (pin "A") (pinfunction "A_A") (pintype "passive"))
      (node (ref "S34") (pin "4") (pinfunction "O1_4") (pintype "passive"))
    )
    (net (code "87") (name "Net-(S35-O)") (class "Default")
      (node (ref "D69") (pin "A") (pinfunction "A_A") (pintype "passive"))
      (node (ref "S35") (pin "1") (pinfunction "O_1") (pintype "passive"))
    )
    (net (code "88") (name "Net-(S35-O1)") (class "Default")
      (node (ref "D70") (pin "A") (pinfunction "A_A") (pintype "passive"))
      (node (ref "S35") (pin "4") (pinfunction "O1_4") (pintype "passive"))
    )
    (net (code "89") (name "Net-(S36-O)") (class "Default")
      (node (ref "D71") (pin "A") (pinfunction "A_A") (pintype "passive"))
      (node (ref "S36") (pin "1") (pinfunction "O_1") (pintype "passive"))
    )
    (net (code "90") (name "Net-(S36-O1)") (class "Default")
      (node (ref "D72") (pin "A") (pinfunction "A_A") (pintype "passive"))
      (node (ref "S36") (pin "4") (pinfunction "O1_4") (pintype "passive"))
    )
    (net (code "91") (name "Net-(S37-O)") (class "Default")
      (node (ref "D73") (pin "A") (pinfunction "A_A") (pintype "passive"))
      (node (ref "S37") (pin "1") (pinfunction "O_1") (pintype "passive"))
    )
    (net (code "92") (name "Net-(S37-O1)") (class "Default")
      (node (ref "D74") (pin "A") (pinfunction "A_A") (pintype "passive"))
      (node (ref "S37") (pin "4") (pinfunction "O1_4") (pintype "passive"))
    )
    (net (code "93") (name "Net-(S38-O)") (class "Default")
      (node (ref "D75") (pin "A") (pinfunction "A_A") (pintype "passive"))
      (node (ref "S38") (pin "1") (pinfunction "O_1") (pintype "passive"))
    )
    (net (code "94") (name "Net-(S38-O1)") (class "Default")
      (node (ref "D76") (pin "A") (pinfunction "A_A") (pintype "passive"))
      (node (ref "S38") (pin "4") (pinfunction "O1_4") (pintype "passive"))
    )
    (net (code "95") (name "Net-(S39-O)") (class "Default")
      (node (ref "D77") (pin "A") (pinfunction "A_A") (pintype "passive"))
      (node (ref "S39") (pin "1") (pinfunction "O_1") (pintype "passive"))
    )
    (net (code "96") (name "Net-(S39-O1)") (class "Default")
      (node (ref "D78") (pin "A") (pinfunction "A_A") (pintype "passive"))
      (node (ref "S39") (pin "4") (pinfunction "O1_4") (pintype "passive"))
    )
    (net (code "97") (name "Net-(S40-O)") (class "Default")
      (node (ref "D79") (pin "A") (pinfunction "A_A") (pintype "passive"))
      (node (ref "S40") (pin "1") (pinfunction "O_1") (pintype "passive"))
    )
    (net (code "98") (name "Net-(S40-O1)") (class "Default")
      (node (ref "D80") (pin "A") (pinfunction "A_A") (pintype "passive"))
      (node (ref "S40") (pin "4") (pinfunction "O1_4") (pintype "passive"))
    )
    (net (code "99") (name "Net-(S41-O)") (class "Default")
      (node (ref "D81") (pin "A") (pinfunction "A_A") (pintype "passive"))
      (node (ref "S41") (pin "1") (pinfunction "O_1") (pintype "passive"))
    )
    (net (code "100") (name "Net-(S41-O1)") (class "Default")
      (node (ref "D82") (pin "A") (pinfunction "A_A") (pintype "passive"))
      (node (ref "S41") (pin "4") (pinfunction "O1_4") (pintype "passive"))
    )
    (net (code "101") (name "Net-(S41-P)") (class "Default")
      (node (ref "S41") (pin "2") (pinfunction "P_2") (pintype "passive"))
      (node (ref "S42") (pin "2") (pinfunction "P_2") (pintype "passive"))
      (node (ref "S43") (pin "2") (pinfunction "P_2") (pintype "passive"))
      (node (ref "S44") (pin "2") (pinfunction "P_2") (pintype "passive"))
      (node (ref "S45") (pin "2") (pinfunction "P_2") (pintype "passive"))
      (node (ref "S46") (pin "2") (pinfunction "P_2") (pintype "passive"))
      (node (ref "S47") (pin "2") (pinfunction "P_2") (pintype "passive"))
      (node (ref "S48") (pin "2") (pinfunction "P_2") (pintype "passive"))
      (node (ref "X1") (pin "15") (pinfunction "15_15") (pintype "passive"))
    )
    (net (code "102") (name "Net-(S41-P1)") (class "Default")
      (node (ref "S41") (pin "5") (pinfunction "P1_5") (pintype "passive"))
      (node (ref "S42") (pin "5") (pinfunction "P1_5") (pintype "passive"))
      (node (ref "S43") (pin "5") (pinfunction "P1_5") (pintype "passive"))
      (node (ref "S44") (pin "5") (pinfunction "P1_5") (pintype "passive"))
      (node (ref "S45") (pin "5") (pinfunction "P1_5") (pintype "passive"))
      (node (ref "S46") (pin "5") (pinfunction "P1_5") (pintype "passive"))
      (node (ref "S47") (pin "5") (pinfunction "P1_5") (pintype "passive"))
      (node (ref "S48") (pin "5") (pinfunction "P1_5") (pintype "passive"))
      (node (ref "X1") (pin "16") (pinfunction "16_16") (pintype "passive"))
    )
    (net (code "103") (name "Net-(S42-O)") (class "Default")
      (node (ref "D83") (pin "A") (pinfunction "A_A") (pintype "passive"))
      (node (ref "S42") (pin "1") (pinfunction "O_1") (pintype "passive"))
    )
    (net (code "104") (name "Net-(S42-O1)") (class "Default")
      (node (ref "D84") (pin "A") (pinfunction "A_A") (pintype "passive"))
      (node (ref "S42") (pin "4") (pinfunction "O1_4") (pintype "passive"))
    )
    (net (code "105") (name "Net-(S43-O)") (class "Default")
      (node (ref "D85") (pin "A") (pinfunction "A_A") (pintype "passive"))
      (node (ref "S43") (pin "1") (pinfunction "O_1") (pintype "passive"))
    )
    (net (code "106") (name "Net-(S43-O1)") (class "Default")
      (node (ref "D86") (pin "A") (pinfunction "A_A") (pintype "passive"))
      (node (ref "S43") (pin "4") (pinfunction "O1_4") (pintype "passive"))
    )
    (net (code "107") (name "Net-(S44-O)") (class "Default")
      (node (ref "D87") (pin "A") (pinfunction "A_A") (pintype "passive"))
      (node (ref "S44") (pin "1") (pinfunction "O_1") (pintype "passive"))
    )
    (net (code "108") (name "Net-(S44-O1)") (class "Default")
      (node (ref "D88") (pin "A") (pinfunction "A_A") (pintype "passive"))
      (node (ref "S44") (pin "4") (pinfunction "O1_4") (pintype "passive"))
    )
    (net (code "109") (name "Net-(S45-O)") (class "Default")
      (node (ref "D89") (pin "A") (pinfunction "A_A") (pintype "passive"))
      (node (ref "S45") (pin "1") (pinfunction "O_1") (pintype "passive"))
    )
    (net (code "110") (name "Net-(S45-O1)") (class "Default")
      (node (ref "D90") (pin "A") (pinfunction "A_A") (pintype "passive"))
      (node (ref "S45") (pin "4") (pinfunction "O1_4") (pintype "passive"))
    )
    (net (code "111") (name "Net-(S46-O)") (class "Default")
      (node (ref "D91") (pin "A") (pinfunction "A_A") (pintype "passive"))
      (node (ref "S46") (pin "1") (pinfunction "O_1") (pintype "passive"))
    )
    (net (code "112") (name "Net-(S46-O1)") (class "Default")
      (node (ref "D92") (pin "A") (pinfunction "A_A") (pintype "passive"))
      (node (ref "S46") (pin "4") (pinfunction "O1_4") (pintype "passive"))
    )
    (net (code "113") (name "Net-(S47-O)") (class "Default")
      (node (ref "D93") (pin "A") (pinfunction "A_A") (pintype "passive"))
      (node (ref "S47") (pin "1") (pinfunction "O_1") (pintype "passive"))
    )
    (net (code "114") (name "Net-(S47-O1)") (class "Default")
      (node (ref "D94") (pin "A") (pinfunction "A_A") (pintype "passive"))
      (node (ref "S47") (pin "4") (pinfunction "O1_4") (pintype "passive"))
    )
    (net (code "115") (name "Net-(S48-O)") (class "Default")
      (node (ref "D95") (pin "A") (pinfunction "A_A") (pintype "passive"))
      (node (ref "S48") (pin "1") (pinfunction "O_1") (pintype "passive"))
    )
    (net (code "116") (name "Net-(S48-O1)") (class "Default")
      (node (ref "D96") (pin "A") (pinfunction "A_A") (pintype "passive"))
      (node (ref "S48") (pin "4") (pinfunction "O1_4") (pintype "passive"))
    )
    (net (code "117") (name "Net-(S49-O)") (class "Default")
      (node (ref "D97") (pin "A") (pinfunction "A_A") (pintype "passive"))
      (node (ref "S49") (pin "1") (pinfunction "O_1") (pintype "passive"))
    )
    (net (code "118") (name "Net-(S49-O1)") (class "Default")
      (node (ref "D98") (pin "A") (pinfunction "A_A") (pintype "passive"))
      (node (ref "S49") (pin "4") (pinfunction "O1_4") (pintype "passive"))
    )
    (net (code "119") (name "Net-(S49-P)") (class "Default")
      (node (ref "S49") (pin "2") (pinfunction "P_2") (pintype "passive"))
      (node (ref "X2") (pin "6") (pinfunction "6_6") (pintype "passive"))
    )
    (net (code "120") (name "Net-(S49-P1)") (class "Default")
      (node (ref "S49") (pin "5") (pinfunction "P1_5") (pintype "passive"))
      (node (ref "X2") (pin "5") (pinfunction "5_5") (pintype "passive"))
    )
    (net (code "121") (name "unconnected-(S1-S-Pad3)") (class "Default")
      (node (ref "S1") (pin "3") (pinfunction "S_3") (pintype "passive"))
    )
    (net (code "122") (name "unconnected-(S1-S1-Pad6)") (class "Default")
      (node (ref "S1") (pin "6") (pinfunction "S1_6") (pintype "passive"))
    )
    (net (code "123") (name "unconnected-(S2-S-Pad3)") (class "Default")
      (node (ref "S2") (pin "3") (pinfunction "S_3") (pintype "passive"))
    )
    (net (code "124") (name "unconnected-(S2-S1-Pad6)") (class "Default")
      (node (ref "S2") (pin "6") (pinfunction "S1_6") (pintype "passive"))
    )
    (net (code "125") (name "unconnected-(S3-S-Pad3)") (class "Default")
      (node (ref "S3") (pin "3") (pinfunction "S_3") (pintype "passive"))
    )
    (net (code "126") (name "unconnected-(S3-S1-Pad6)") (class "Default")
      (node (ref "S3") (pin "6") (pinfunction "S1_6") (pintype "passive"))
    )
    (net (code "127") (name "unconnected-(S4-S-Pad3)") (class "Default")
      (node (ref "S4") (pin "3") (pinfunction "S_3") (pintype "passive"))
    )
    (net (code "128") (name "unconnected-(S4-S1-Pad6)") (class "Default")
      (node (ref "S4") (pin "6") (pinfunction "S1_6") (pintype "passive"))
    )
    (net (code "129") (name "unconnected-(S5-S-Pad3)") (class "Default")
      (node (ref "S5") (pin "3") (pinfunction "S_3") (pintype "passive"))
    )
    (net (code "130") (name "unconnected-(S5-S1-Pad6)") (class "Default")
      (node (ref "S5") (pin "6") (pinfunction "S1_6") (pintype "passive"))
    )
    (net (code "131") (name "unconnected-(S6-S-Pad3)") (class "Default")
      (node (ref "S6") (pin "3") (pinfunction "S_3") (pintype "passive"))
    )
    (net (code "132") (name "unconnected-(S6-S1-Pad6)") (class "Default")
      (node (ref "S6") (pin "6") (pinfunction "S1_6") (pintype "passive"))
    )
    (net (code "133") (name "unconnected-(S7-P-Pad2)") (class "Default")
      (node (ref "S7") (pin "2") (pinfunction "P_2") (pintype "passive"))
    )
    (net (code "134") (name "unconnected-(S7-S-Pad3)") (class "Default")
      (node (ref "S7") (pin "3") (pinfunction "S_3") (pintype "passive"))
    )
    (net (code "135") (name "unconnected-(S7-S1-Pad6)") (class "Default")
      (node (ref "S7") (pin "6") (pinfunction "S1_6") (pintype "passive"))
    )
    (net (code "136") (name "unconnected-(S8-S-Pad3)") (class "Default")
      (node (ref "S8") (pin "3") (pinfunction "S_3") (pintype "passive"))
    )
    (net (code "137") (name "unconnected-(S8-S1-Pad6)") (class "Default")
      (node (ref "S8") (pin "6") (pinfunction "S1_6") (pintype "passive"))
    )
    (net (code "138") (name "unconnected-(S9-S-Pad3)") (class "Default")
      (node (ref "S9") (pin "3") (pinfunction "S_3") (pintype "passive"))
    )
    (net (code "139") (name "unconnected-(S9-S1-Pad6)") (class "Default")
      (node (ref "S9") (pin "6") (pinfunction "S1_6") (pintype "passive"))
    )
    (net (code "140") (name "unconnected-(S10-S-Pad3)") (class "Default")
      (node (ref "S10") (pin "3") (pinfunction "S_3") (pintype "passive"))
    )
    (net (code "141") (name "unconnected-(S10-S1-Pad6)") (class "Default")
      (node (ref "S10") (pin "6") (pinfunction "S1_6") (pintype "passive"))
    )
    (net (code "142") (name "unconnected-(S11-S-Pad3)") (class "Default")
      (node (ref "S11") (pin "3") (pinfunction "S_3") (pintype "passive"))
    )
    (net (code "143") (name "unconnected-(S11-S1-Pad6)") (class "Default")
      (node (ref "S11") (pin "6") (pinfunction "S1_6") (pintype "passive"))
    )
    (net (code "144") (name "unconnected-(S12-S-Pad3)") (class "Default")
      (node (ref "S12") (pin "3") (pinfunction "S_3") (pintype "passive"))
    )
    (net (code "145") (name "unconnected-(S12-S1-Pad6)") (class "Default")
      (node (ref "S12") (pin "6") (pinfunction "S1_6") (pintype "passive"))
    )
    (net (code "146") (name "unconnected-(S13-S-Pad3)") (class "Default")
      (node (ref "S13") (pin "3") (pinfunction "S_3") (pintype "passive"))
    )
    (net (code "147") (name "unconnected-(S13-S1-Pad6)") (class "Default")
      (node (ref "S13") (pin "6") (pinfunction "S1_6") (pintype "passive"))
    )
    (net (code "148") (name "unconnected-(S14-S-Pad3)") (class "Default")
      (node (ref "S14") (pin "3") (pinfunction "S_3") (pintype "passive"))
    )
    (net (code "149") (name "unconnected-(S14-S1-Pad6)") (class "Default")
      (node (ref "S14") (pin "6") (pinfunction "S1_6") (pintype "passive"))
    )
    (net (code "150") (name "unconnected-(S15-S-Pad3)") (class "Default")
      (node (ref "S15") (pin "3") (pinfunction "S_3") (pintype "passive"))
    )
    (net (code "151") (name "unconnected-(S15-S1-Pad6)") (class "Default")
      (node (ref "S15") (pin "6") (pinfunction "S1_6") (pintype "passive"))
    )
    (net (code "152") (name "unconnected-(S16-S-Pad3)") (class "Default")
      (node (ref "S16") (pin "3") (pinfunction "S_3") (pintype "passive"))
    )
    (net (code "153") (name "unconnected-(S16-S1-Pad6)") (class "Default")
      (node (ref "S16") (pin "6") (pinfunction "S1_6") (pintype "passive"))
    )
    (net (code "154") (name "unconnected-(S17-S-Pad3)") (class "Default")
      (node (ref "S17") (pin "3") (pinfunction "S_3") (pintype "passive"))
    )
    (net (code "155") (name "unconnected-(S17-S1-Pad6)") (class "Default")
      (node (ref "S17") (pin "6") (pinfunction "S1_6") (pintype "passive"))
    )
    (net (code "156") (name "unconnected-(S18-S-Pad3)") (class "Default")
      (node (ref "S18") (pin "3") (pinfunction "S_3") (pintype "passive"))
    )
    (net (code "157") (name "unconnected-(S18-S1-Pad6)") (class "Default")
      (node (ref "S18") (pin "6") (pinfunction "S1_6") (pintype "passive"))
    )
    (net (code "158") (name "unconnected-(S19-S-Pad3)") (class "Default")
      (node (ref "S19") (pin "3") (pinfunction "S_3") (pintype "passive"))
    )
    (net (code "159") (name "unconnected-(S19-S1-Pad6)") (class "Default")
      (node (ref "S19") (pin "6") (pinfunction "S1_6") (pintype "passive"))
    )
    (net (code "160") (name "unconnected-(S20-S-Pad3)") (class "Default")
      (node (ref "S20") (pin "3") (pinfunction "S_3") (pintype "passive"))
    )
    (net (code "161") (name "unconnected-(S20-S1-Pad6)") (class "Default")
      (node (ref "S20") (pin "6") (pinfunction "S1_6") (pintype "passive"))
    )
    (net (code "162") (name "unconnected-(S21-S-Pad3)") (class "Default")
      (node (ref "S21") (pin "3") (pinfunction "S_3") (pintype "passive"))
    )
    (net (code "163") (name "unconnected-(S21-S1-Pad6)") (class "Default")
      (node (ref "S21") (pin "6") (pinfunction "S1_6") (pintype "passive"))
    )
    (net (code "164") (name "unconnected-(S22-S-Pad3)") (class "Default")
      (node (ref "S22") (pin "3") (pinfunction "S_3") (pintype "passive"))
    )
    (net (code "165") (name "unconnected-(S22-S1-Pad6)") (class "Default")
      (node (ref "S22") (pin "6") (pinfunction "S1_6") (pintype "passive"))
    )
    (net (code "166") (name "unconnected-(S23-S-Pad3)") (class "Default")
      (node (ref "S23") (pin "3") (pinfunction "S_3") (pintype "passive"))
    )
    (net (code "167") (name "unconnected-(S23-S1-Pad6)") (class "Default")
      (node (ref "S23") (pin "6") (pinfunction "S1_6") (pintype "passive"))
    )
    (net (code "168") (name "unconnected-(S24-S-Pad3)") (class "Default")
      (node (ref "S24") (pin "3") (pinfunction "S_3") (pintype "passive"))
    )
    (net (code "169") (name "unconnected-(S24-S1-Pad6)") (class "Default")
      (node (ref "S24") (pin "6") (pinfunction "S1_6") (pintype "passive"))
    )
    (net (code "170") (name "unconnected-(S25-S-Pad3)") (class "Default")
      (node (ref "S25") (pin "3") (pinfunction "S_3") (pintype "passive"))
    )
    (net (code "171") (name "unconnected-(S25-S1-Pad6)") (class "Default")
      (node (ref "S25") (pin "6") (pinfunction "S1_6") (pintype "passive"))
    )
    (net (code "172") (name "unconnected-(S26-S-Pad3)") (class "Default")
      (node (ref "S26") (pin "3") (pinfunction "S_3") (pintype "passive"))
    )
    (net (code "173") (name "unconnected-(S26-S1-Pad6)") (class "Default")
      (node (ref "S26") (pin "6") (pinfunction "S1_6") (pintype "passive"))
    )
    (net (code "174") (name "unconnected-(S27-S-Pad3)") (class "Default")
      (node (ref "S27") (pin "3") (pinfunction "S_3") (pintype "passive"))
    )
    (net (code "175") (name "unconnected-(S27-S1-Pad6)") (class "Default")
      (node (ref "S27") (pin "6") (pinfunction "S1_6") (pintype "passive"))
    )
    (net (code "176") (name "unconnected-(S28-S-Pad3)") (class "Default")
      (node (ref "S28") (pin "3") (pinfunction "S_3") (pintype "passive"))
    )
    (net (code "177") (name "unconnected-(S28-S1-Pad6)") (class "Default")
      (node (ref "S28") (pin "6") (pinfunction "S1_6") (pintype "passive"))
    )
    (net (code "178") (name "unconnected-(S29-S-Pad3)") (class "Default")
      (node (ref "S29") (pin "3") (pinfunction "S_3") (pintype "passive"))
    )
    (net (code "179") (name "unconnected-(S29-S1-Pad6)") (class "Default")
      (node (ref "S29") (pin "6") (pinfunction "S1_6") (pintype "passive"))
    )
    (net (code "180") (name "unconnected-(S30-S-Pad3)") (class "Default")
      (node (ref "S30") (pin "3") (pinfunction "S_3") (pintype "passive"))
    )
    (net (code "181") (name "unconnected-(S30-S1-Pad6)") (class "Default")
      (node (ref "S30") (pin "6") (pinfunction "S1_6") (pintype "passive"))
    )
    (net (code "182") (name "unconnected-(S31-S-Pad3)") (class "Default")
      (node (ref "S31") (pin "3") (pinfunction "S_3") (pintype "passive"))
    )
    (net (code "183") (name "unconnected-(S31-S1-Pad6)") (class "Default")
      (node (ref "S31") (pin "6") (pinfunction "S1_6") (pintype "passive"))
    )
    (net (code "184") (name "unconnected-(S32-S-Pad3)") (class "Default")
      (node (ref "S32") (pin "3") (pinfunction "S_3") (pintype "passive"))
    )
    (net (code "185") (name "unconnected-(S32-S1-Pad6)") (class "Default")
      (node (ref "S32") (pin "6") (pinfunction "S1_6") (pintype "passive"))
    )
    (net (code "186") (name "unconnected-(S33-S-Pad3)") (class "Default")
      (node (ref "S33") (pin "3") (pinfunction "S_3") (pintype "passive"))
    )
    (net (code "187") (name "unconnected-(S33-S1-Pad6)") (class "Default")
      (node (ref "S33") (pin "6") (pinfunction "S1_6") (pintype "passive"))
    )
    (net (code "188") (name "unconnected-(S34-S-Pad3)") (class "Default")
      (node (ref "S34") (pin "3") (pinfunction "S_3") (pintype "passive"))
    )
    (net (code "189") (name "unconnected-(S34-S1-Pad6)") (class "Default")
      (node (ref "S34") (pin "6") (pinfunction "S1_6") (pintype "passive"))
    )
    (net (code "190") (name "unconnected-(S35-S-Pad3)") (class "Default")
      (node (ref "S35") (pin "3") (pinfunction "S_3") (pintype "passive"))
    )
    (net (code "191") (name "unconnected-(S35-S1-Pad6)") (class "Default")
      (node (ref "S35") (pin "6") (pinfunction "S1_6") (pintype "passive"))
    )
    (net (code "192") (name "unconnected-(S36-S-Pad3)") (class "Default")
      (node (ref "S36") (pin "3") (pinfunction "S_3") (pintype "passive"))
    )
    (net (code "193") (name "unconnected-(S36-S1-Pad6)") (class "Default")
      (node (ref "S36") (pin "6") (pinfunction "S1_6") (pintype "passive"))
    )
    (net (code "194") (name "unconnected-(S37-S-Pad3)") (class "Default")
      (node (ref "S37") (pin "3") (pinfunction "S_3") (pintype "passive"))
    )
    (net (code "195") (name "unconnected-(S37-S1-Pad6)") (class "Default")
      (node (ref "S37") (pin "6") (pinfunction "S1_6") (pintype "passive"))
    )
    (net (code "196") (name "unconnected-(S38-S-Pad3)") (class "Default")
      (node (ref "S38") (pin "3") (pinfunction "S_3") (pintype "passive"))
    )
    (net (code "197") (name "unconnected-(S38-S1-Pad6)") (class "Default")
      (node (ref "S38") (pin "6") (pinfunction "S1_6") (pintype "passive"))
    )
    (net (code "198") (name "unconnected-(S39-S-Pad3)") (class "Default")
      (node (ref "S39") (pin "3") (pinfunction "S_3") (pintype "passive"))
    )
    (net (code "199") (name "unconnected-(S39-S1-Pad6)") (class "Default")
      (node (ref "S39") (pin "6") (pinfunction "S1_6") (pintype "passive"))
    )
    (net (code "200") (name "unconnected-(S40-S-Pad3)") (class "Default")
      (node (ref "S40") (pin "3") (pinfunction "S_3") (pintype "passive"))
    )
    (net (code "201") (name "unconnected-(S40-S1-Pad6)") (class "Default")
      (node (ref "S40") (pin "6") (pinfunction "S1_6") (pintype "passive"))
    )
    (net (code "202") (name "unconnected-(S41-S-Pad3)") (class "Default")
      (node (ref "S41") (pin "3") (pinfunction "S_3") (pintype "passive"))
    )
    (net (code "203") (name "unconnected-(S41-S1-Pad6)") (class "Default")
      (node (ref "S41") (pin "6") (pinfunction "S1_6") (pintype "passive"))
    )
    (net (code "204") (name "unconnected-(S42-S-Pad3)") (class "Default")
      (node (ref "S42") (pin "3") (pinfunction "S_3") (pintype "passive"))
    )
    (net (code "205") (name "unconnected-(S42-S1-Pad6)") (class "Default")
      (node (ref "S42") (pin "6") (pinfunction "S1_6") (pintype "passive"))
    )
    (net (code "206") (name "unconnected-(S43-S-Pad3)") (class "Default")
      (node (ref "S43") (pin "3") (pinfunction "S_3") (pintype "passive"))
    )
    (net (code "207") (name "unconnected-(S43-S1-Pad6)") (class "Default")
      (node (ref "S43") (pin "6") (pinfunction "S1_6") (pintype "passive"))
    )
    (net (code "208") (name "unconnected-(S44-S-Pad3)") (class "Default")
      (node (ref "S44") (pin "3") (pinfunction "S_3") (pintype "passive"))
    )
    (net (code "209") (name "unconnected-(S44-S1-Pad6)") (class "Default")
      (node (ref "S44") (pin "6") (pinfunction "S1_6") (pintype "passive"))
    )
    (net (code "210") (name "unconnected-(S45-S-Pad3)") (class "Default")
      (node (ref "S45") (pin "3") (pinfunction "S_3") (pintype "passive"))
    )
    (net (code "211") (name "unconnected-(S45-S1-Pad6)") (class "Default")
      (node (ref "S45") (pin "6") (pinfunction "S1_6") (pintype "passive"))
    )
    (net (code "212") (name "unconnected-(S46-S-Pad3)") (class "Default")
      (node (ref "S46") (pin "3") (pinfunction "S_3") (pintype "passive"))
    )
    (net (code "213") (name "unconnected-(S46-S1-Pad6)") (class "Default")
      (node (ref "S46") (pin "6") (pinfunction "S1_6") (pintype "passive"))
    )
    (net (code "214") (name "unconnected-(S47-S-Pad3)") (class "Default")
      (node (ref "S47") (pin "3") (pinfunction "S_3") (pintype "passive"))
    )
    (net (code "215") (name "unconnected-(S47-S1-Pad6)") (class "Default")
      (node (ref "S47") (pin "6") (pinfunction "S1_6") (pintype "passive"))
    )
    (net (code "216") (name "unconnected-(S48-S-Pad3)") (class "Default")
      (node (ref "S48") (pin "3") (pinfunction "S_3") (pintype "passive"))
    )
    (net (code "217") (name "unconnected-(S48-S1-Pad6)") (class "Default")
      (node (ref "S48") (pin "6") (pinfunction "S1_6") (pintype "passive"))
    )
    (net (code "218") (name "unconnected-(S49-S-Pad3)") (class "Default")
      (node (ref "S49") (pin "3") (pinfunction "S_3") (pintype "passive"))
    )
    (net (code "219") (name "unconnected-(S49-S1-Pad6)") (class "Default")
      (node (ref "S49") (pin "6") (pinfunction "S1_6") (pintype "passive"))
    )
  )
)
